# Collection_1.net
KiCad netlist of a schematic drawn in EAGLE
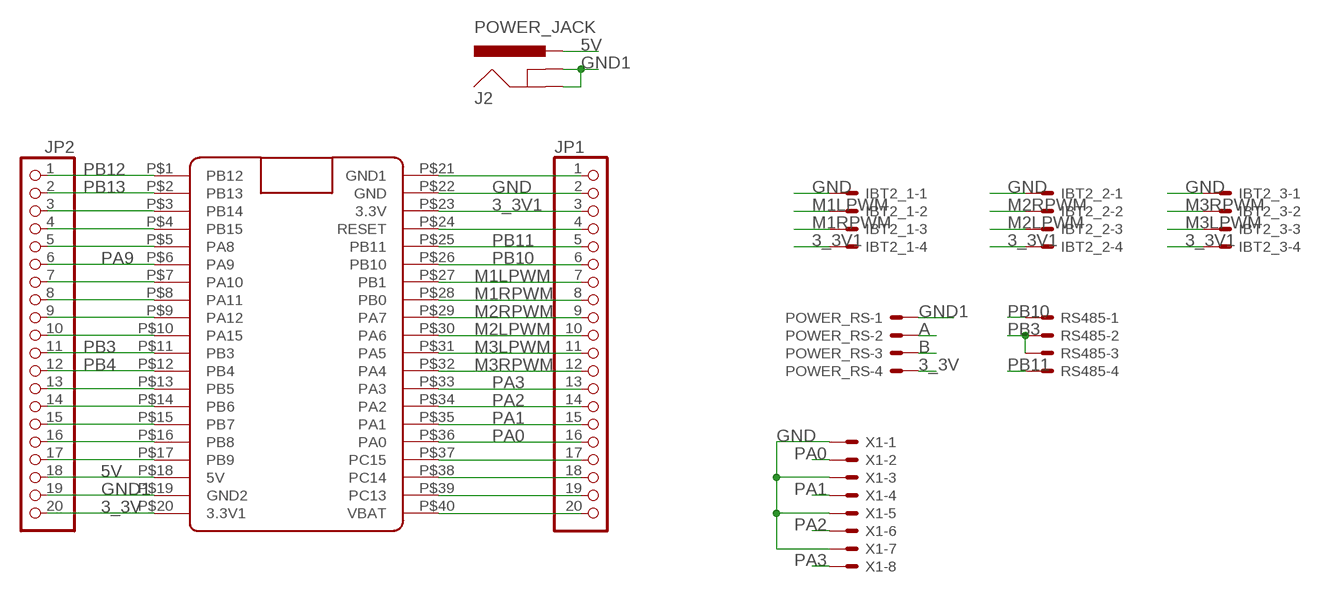
[diagram p0: schematic, sheet 1]

(export (version "E")
  (design (tool "Eeschema 10.0.6"))
  (components
    (comp (ref "IBT2_1")
      (value "JST-XH-04-PIN-LONG-PAD")
      (footprint "eagle-import:JST-XH-04-PACKAGE-LONG-PAD")
      (libsource (lib "eagle-import") (part "JST-XH-04-PIN-LONG-PAD"))
    )
    (comp (ref "IBT2_2")
      (value "JST-XH-04-PIN-LONG-PAD")
      (footprint "eagle-import:JST-XH-04-PACKAGE-LONG-PAD")
      (libsource (lib "eagle-import") (part "JST-XH-04-PIN-LONG-PAD"))
    )
    (comp (ref "IBT2_3")
      (value "JST-XH-04-PIN-LONG-PAD")
      (footprint "eagle-import:JST-XH-04-PACKAGE-LONG-PAD")
      (libsource (lib "eagle-import") (part "JST-XH-04-PIN-LONG-PAD"))
    )
    (comp (ref "J2")
      (value "POWER_JACK")
      (footprint "eagle-import:POWER_JACK")
      (fields (field (name "MPN") "PJ-202A"))
      (libsource (lib "eagle-import") (part "POWER_JACK"))
    )
    (comp (ref "JP1")
      (value "PINHD-1X20")
      (footprint "eagle-import:1X20")
      (libsource (lib "eagle-import") (part "PINHD-1X20"))
    )
    (comp (ref "JP2")
      (value "PINHD-1X20")
      (footprint "eagle-import:1X20")
      (libsource (lib "eagle-import") (part "PINHD-1X20"))
    )
    (comp (ref "POWER_RS")
      (value "JST-XH-04-PIN-LONG-PAD")
      (footprint "eagle-import:JST-XH-04-PACKAGE-LONG-PAD")
      (libsource (lib "eagle-import") (part "JST-XH-04-PIN-LONG-PAD"))
    )
    (comp (ref "RS485")
      (value "JST-XH-04-PIN-LONG-PAD")
      (footprint "eagle-import:JST-XH-04-PACKAGE-LONG-PAD")
      (libsource (lib "eagle-import") (part "JST-XH-04-PIN-LONG-PAD"))
    )
    (comp (ref "U$1")
      (value "BLUE_PILL")
      (footprint "eagle-import:BLUE_PILL")
      (libsource (lib "eagle-import") (part "BLUE_PILL"))
    )
    (comp (ref "X1")
      (value "JST-XH-08-PIN-LONG-PAD")
      (footprint "eagle-import:JST-XH-08-PACKAGE-LONG-PAD")
      (libsource (lib "eagle-import") (part "JST-XH-08-PIN-LONG-PAD"))
    )
  )
  (nets
    (net (code "1") (name "/3_3V") (class "Default")
      (node (ref "JP2") (pin "20") (pinfunction "20_20") (pintype "passive"))
      (node (ref "POWER_RS") (pin "4") (pinfunction "S_4") (pintype "passive"))
      (node (ref "U$1") (pin "P$20") (pinfunction "3.3V1_P$20") (pintype "bidirectional"))
    )
    (net (code "2") (name "/3_3V1") (class "Default")
      (node (ref "IBT2_1") (pin "4") (pinfunction "S_4") (pintype "passive"))
      (node (ref "IBT2_2") (pin "4") (pinfunction "S_4") (pintype "passive"))
      (node (ref "IBT2_3") (pin "4") (pinfunction "S_4") (pintype "passive"))
      (node (ref "JP1") (pin "3") (pinfunction "3_3") (pintype "passive"))
      (node (ref "U$1") (pin "P$23") (pinfunction "3.3V_P$23") (pintype "bidirectional"))
    )
    (net (code "3") (name "/5V") (class "Default")
      (node (ref "J2") (pin "PWR") (pinfunction "PWR_PWR") (pintype "bidirectional"))
      (node (ref "JP2") (pin "18") (pinfunction "18_18") (pintype "passive"))
      (node (ref "U$1") (pin "P$18") (pinfunction "5V_P$18") (pintype "bidirectional"))
    )
    (net (code "4") (name "/A") (class "Default")
      (node (ref "POWER_RS") (pin "2") (pinfunction "S_2") (pintype "passive"))
    )
    (net (code "5") (name "/B") (class "Default")
      (node (ref "POWER_RS") (pin "3") (pinfunction "S_3") (pintype "passive"))
    )
    (net (code "6") (name "/GND") (class "Default")
      (node (ref "IBT2_1") (pin "1") (pinfunction "S_1") (pintype "passive"))
      (node (ref "IBT2_2") (pin "1") (pinfunction "S_1") (pintype "passive"))
      (node (ref "IBT2_3") (pin "1") (pinfunction "S_1") (pintype "passive"))
      (node (ref "JP1") (pin "2") (pinfunction "2_2") (pintype "passive"))
      (node (ref "U$1") (pin "P$22") (pinfunction "GND_P$22") (pintype "bidirectional"))
      (node (ref "X1") (pin "1") (pinfunction "S_1") (pintype "passive"))
      (node (ref "X1") (pin "3") (pinfunction "S_3") (pintype "passive"))
      (node (ref "X1") (pin "5") (pinfunction "S_5") (pintype "passive"))
      (node (ref "X1") (pin "7") (pinfunction "S_7") (pintype "passive"))
    )
    (net (code "7") (name "/GND1") (class "Default")
      (node (ref "J2") (pin "GND") (pinfunction "GND_GND") (pintype "bidirectional"))
      (node (ref "J2") (pin "GNDBREAK") (pinfunction "GNDBREAK_GNDBREAK") (pintype "bidirectional"))
      (node (ref "JP2") (pin "19") (pinfunction "19_19") (pintype "passive"))
      (node (ref "POWER_RS") (pin "1") (pinfunction "S_1") (pintype "passive"))
      (node (ref "U$1") (pin "P$19") (pinfunction "GND2_P$19") (pintype "bidirectional"))
    )
    (net (code "8") (name "/M1LPWM") (class "Default")
      (node (ref "IBT2_1") (pin "2") (pinfunction "S_2") (pintype "passive"))
      (node (ref "JP1") (pin "7") (pinfunction "7_7") (pintype "passive"))
      (node (ref "U$1") (pin "P$27") (pinfunction "PB1_P$27") (pintype "bidirectional"))
    )
    (net (code "9") (name "/M1RPWM") (class "Default")
      (node (ref "IBT2_1") (pin "3") (pinfunction "S_3") (pintype "passive"))
      (node (ref "JP1") (pin "8") (pinfunction "8_8") (pintype "passive"))
      (node (ref "U$1") (pin "P$28") (pinfunction "PB0_P$28") (pintype "bidirectional"))
    )
    (net (code "10") (name "/M2LPWM") (class "Default")
      (node (ref "IBT2_2") (pin "3") (pinfunction "S_3") (pintype "passive"))
      (node (ref "JP1") (pin "10") (pinfunction "10_10") (pintype "passive"))
      (node (ref "U$1") (pin "P$30") (pinfunction "PA6_P$30") (pintype "bidirectional"))
    )
    (net (code "11") (name "/M2RPWM") (class "Default")
      (node (ref "IBT2_2") (pin "2") (pinfunction "S_2") (pintype "passive"))
      (node (ref "JP1") (pin "9") (pinfunction "9_9") (pintype "passive"))
      (node (ref "U$1") (pin "P$29") (pinfunction "PA7_P$29") (pintype "bidirectional"))
    )
    (net (code "12") (name "/M3LPWM") (class "Default")
      (node (ref "IBT2_3") (pin "3") (pinfunction "S_3") (pintype "passive"))
      (node (ref "JP1") (pin "11") (pinfunction "11_11") (pintype "passive"))
      (node (ref "U$1") (pin "P$31") (pinfunction "PA5_P$31") (pintype "bidirectional"))
    )
    (net (code "13") (name "/M3RPWM") (class "Default")
      (node (ref "IBT2_3") (pin "2") (pinfunction "S_2") (pintype "passive"))
      (node (ref "JP1") (pin "12") (pinfunction "12_12") (pintype "passive"))
      (node (ref "U$1") (pin "P$32") (pinfunction "PA4_P$32") (pintype "bidirectional"))
    )
    (net (code "14") (name "/PA0") (class "Default")
      (node (ref "JP1") (pin "16") (pinfunction "16_16") (pintype "passive"))
      (node (ref "U$1") (pin "P$36") (pinfunction "PA0_P$36") (pintype "bidirectional"))
      (node (ref "X1") (pin "2") (pinfunction "S_2") (pintype "passive"))
    )
    (net (code "15") (name "/PA1") (class "Default")
      (node (ref "JP1") (pin "15") (pinfunction "15_15") (pintype "passive"))
      (node (ref "U$1") (pin "P$35") (pinfunction "PA1_P$35") (pintype "bidirectional"))
      (node (ref "X1") (pin "4") (pinfunction "S_4") (pintype "passive"))
    )
    (net (code "16") (name "/PA2") (class "Default")
      (node (ref "JP1") (pin "14") (pinfunction "14_14") (pintype "passive"))
      (node (ref "U$1") (pin "P$34") (pinfunction "PA2_P$34") (pintype "bidirectional"))
      (node (ref "X1") (pin "6") (pinfunction "S_6") (pintype "passive"))
    )
    (net (code "17") (name "/PA3") (class "Default")
      (node (ref "JP1") (pin "13") (pinfunction "13_13") (pintype "passive"))
      (node (ref "U$1") (pin "P$33") (pinfunction "PA3_P$33") (pintype "bidirectional"))
      (node (ref "X1") (pin "8") (pinfunction "S_8") (pintype "passive"))
    )
    (net (code "18") (name "/PA9") (class "Default")
      (node (ref "JP2") (pin "6") (pinfunction "6_6") (pintype "passive"))
      (node (ref "U$1") (pin "P$6") (pinfunction "PA9_P$6") (pintype "bidirectional"))
    )
    (net (code "19") (name "/PB3") (class "Default")
      (node (ref "JP2") (pin "11") (pinfunction "11_11") (pintype "passive"))
      (node (ref "RS485") (pin "2") (pinfunction "S_2") (pintype "passive"))
      (node (ref "RS485") (pin "3") (pinfunction "S_3") (pintype "passive"))
      (node (ref "U$1") (pin "P$11") (pinfunction "PB3_P$11") (pintype "bidirectional"))
    )
    (net (code "20") (name "/PB4") (class "Default")
      (node (ref "JP2") (pin "12") (pinfunction "12_12") (pintype "passive"))
      (node (ref "U$1") (pin "P$12") (pinfunction "PB4_P$12") (pintype "bidirectional"))
    )
    (net (code "21") (name "/PB10") (class "Default")
      (node (ref "JP1") (pin "6") (pinfunction "6_6") (pintype "passive"))
      (node (ref "RS485") (pin "1") (pinfunction "S_1") (pintype "passive"))
      (node (ref "U$1") (pin "P$26") (pinfunction "PB10_P$26") (pintype "bidirectional"))
    )
    (net (code "22") (name "/PB11") (class "Default")
      (node (ref "JP1") (pin "5") (pinfunction "5_5") (pintype "passive"))
      (node (ref "RS485") (pin "4") (pinfunction "S_4") (pintype "passive"))
      (node (ref "U$1") (pin "P$25") (pinfunction "PB11_P$25") (pintype "bidirectional"))
    )
    (net (code "23") (name "/PB12") (class "Default")
      (node (ref "JP2") (pin "1") (pinfunction "1_1") (pintype "passive"))
      (node (ref "U$1") (pin "P$1") (pinfunction "PB12_P$1") (pintype "bidirectional"))
    )
    (net (code "24") (name "/PB13") (class "Default")
      (node (ref "JP2") (pin "2") (pinfunction "2_2") (pintype "passive"))
      (node (ref "U$1") (pin "P$2") (pinfunction "PB13_P$2") (pintype "bidirectional"))
    )
    (net (code "25") (name "Net-(U$1-GND1)") (class "Default")
      (node (ref "JP1") (pin "1") (pinfunction "1_1") (pintype "passive"))
      (node (ref "U$1") (pin "P$21") (pinfunction "GND1_P$21") (pintype "power_in"))
    )
    (net (code "26") (name "Net-(U$1-PA8)") (class "Default")
      (node (ref "JP2") (pin "5") (pinfunction "5_5") (pintype "passive"))
      (node (ref "U$1") (pin "P$5") (pinfunction "PA8_P$5") (pintype "bidirectional"))
    )
    (net (code "27") (name "Net-(U$1-PA10)") (class "Default")
      (node (ref "JP2") (pin "7") (pinfunction "7_7") (pintype "passive"))
      (node (ref "U$1") (pin "P$7") (pinfunction "PA10_P$7") (pintype "bidirectional"))
    )
    (net (code "28") (name "Net-(U$1-PA11)") (class "Default")
      (node (ref "JP2") (pin "8") (pinfunction "8_8") (pintype "passive"))
      (node (ref "U$1") (pin "P$8") (pinfunction "PA11_P$8") (pintype "bidirectional"))
    )
    (net (code "29") (name "Net-(U$1-PA12)") (class "Default")
      (node (ref "JP2") (pin "9") (pinfunction "9_9") (pintype "passive"))
      (node (ref "U$1") (pin "P$9") (pinfunction "PA12_P$9") (pintype "bidirectional"))
    )
    (net (code "30") (name "Net-(U$1-PA15)") (class "Default")
      (node (ref "JP2") (pin "10") (pinfunction "10_10") (pintype "passive"))
      (node (ref "U$1") (pin "P$10") (pinfunction "PA15_P$10") (pintype "bidirectional"))
    )
    (net (code "31") (name "Net-(U$1-PB5)") (class "Default")
      (node (ref "JP2") (pin "13") (pinfunction "13_13") (pintype "passive"))
      (node (ref "U$1") (pin "P$13") (pinfunction "PB5_P$13") (pintype "bidirectional"))
    )
    (net (code "32") (name "Net-(U$1-PB6)") (class "Default")
      (node (ref "JP2") (pin "14") (pinfunction "14_14") (pintype "passive"))
      (node (ref "U$1") (pin "P$14") (pinfunction "PB6_P$14") (pintype "bidirectional"))
    )
    (net (code "33") (name "Net-(U$1-PB7)") (class "Default")
      (node (ref "JP2") (pin "15") (pinfunction "15_15") (pintype "passive"))
      (node (ref "U$1") (pin "P$15") (pinfunction "PB7_P$15") (pintype "bidirectional"))
    )
    (net (code "34") (name "Net-(U$1-PB8)") (class "Default")
      (node (ref "JP2") (pin "16") (pinfunction "16_16") (pintype "passive"))
      (node (ref "U$1") (pin "P$16") (pinfunction "PB8_P$16") (pintype "bidirectional"))
    )
    (net (code "35") (name "Net-(U$1-PB9)") (class "Default")
      (node (ref "JP2") (pin "17") (pinfunction "17_17") (pintype "passive"))
      (node (ref "U$1") (pin "P$17") (pinfunction "PB9_P$17") (pintype "bidirectional"))
    )
    (net (code "36") (name "Net-(U$1-PB14)") (class "Default")
      (node (ref "JP2") (pin "3") (pinfunction "3_3") (pintype "passive"))
      (node (ref "U$1") (pin "P$3") (pinfunction "PB14_P$3") (pintype "bidirectional"))
    )
    (net (code "37") (name "Net-(U$1-PB15)") (class "Default")
      (node (ref "JP2") (pin "4") (pinfunction "4_4") (pintype "passive"))
      (node (ref "U$1") (pin "P$4") (pinfunction "PB15_P$4") (pintype "bidirectional"))
    )
    (net (code "38") (name "Net-(U$1-PC13)") (class "Default")
      (node (ref "JP1") (pin "19") (pinfunction "19_19") (pintype "passive"))
      (node (ref "U$1") (pin "P$39") (pinfunction "PC13_P$39") (pintype "bidirectional"))
    )
    (net (code "39") (name "Net-(U$1-PC14)") (class "Default")
      (node (ref "JP1") (pin "18") (pinfunction "18_18") (pintype "passive"))
      (node (ref "U$1") (pin "P$38") (pinfunction "PC14_P$38") (pintype "bidirectional"))
    )
    (net (code "40") (name "Net-(U$1-PC15)") (class "Default")
      (node (ref "JP1") (pin "17") (pinfunction "17_17") (pintype "passive"))
      (node (ref "U$1") (pin "P$37") (pinfunction "PC15_P$37") (pintype "bidirectional"))
    )
    (net (code "41") (name "Net-(U$1-RESET)") (class "Default")
      (node (ref "JP1") (pin "4") (pinfunction "4_4") (pintype "passive"))
      (node (ref "U$1") (pin "P$24") (pinfunction "RESET_P$24") (pintype "bidirectional"))
    )
    (net (code "42") (name "Net-(U$1-VBAT)") (class "Default")
      (node (ref "JP1") (pin "20") (pinfunction "20_20") (pintype "passive"))
      (node (ref "U$1") (pin "P$40") (pinfunction "VBAT_P$40") (pintype "bidirectional"))
    )
  )
)
